# GateDriver.net
KiCad netlist of a schematic drawn in Altium Designer
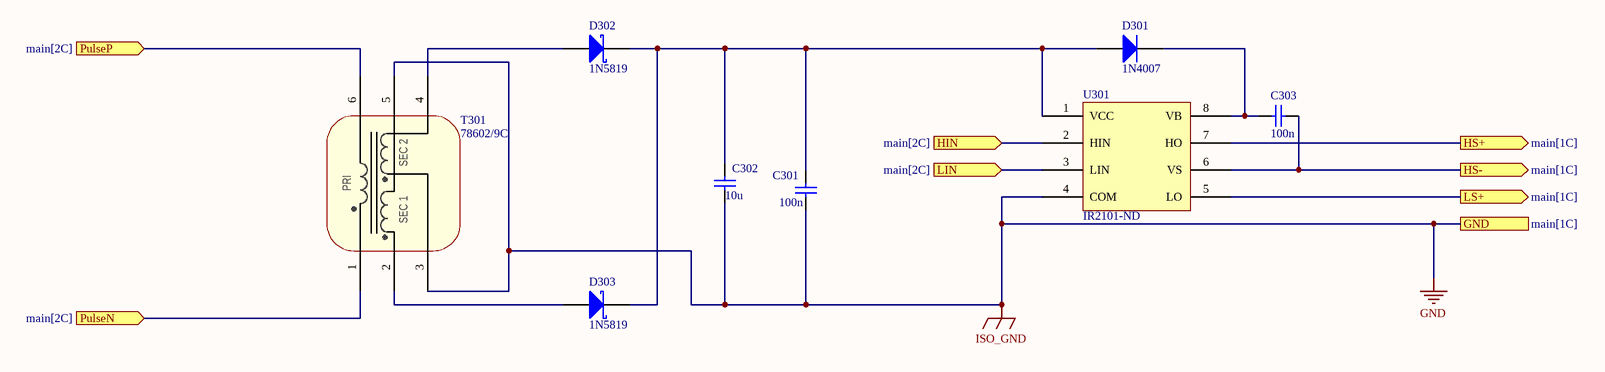
[diagram p0: GateDriver.SchDoc]

(export (version "E")
  (design (tool "Eeschema 10.0.6"))
  (components
    (comp (ref "C301")
      (value "100n")
      (footprint "CAP_1206")
      (description "Non Polarized Capacitor, SMD, 1206")
      (libsource (lib "Resistors and Capacitors") (part "CAPN 1206"))
    )
    (comp (ref "C302")
      (value "10u")
      (footprint "CAP_1206")
      (description "Non Polarized Capacitor, SMD, 1206")
      (libsource (lib "Resistors and Capacitors") (part "CAPN 1206"))
    )
    (comp (ref "C303")
      (value "100n")
      (footprint "RAD-0.2_AUT")
      (description "Non Polarized Capacitor, Multilayer Ceramic Dipped Radial, Pitch 200mil")
      (libsource (lib "Resistors and Capacitors") (part "CAPN RAD0.2"))
    )
    (comp (ref "D301")
      (value "1N4007")
      (footprint "DIODE0.4_AUT")
      (description "Diode, Standard, 1A, 1000v")
      (libsource (lib "Diodes") (part "1N4007"))
    )
    (comp (ref "D302")
      (value "1N5819")
      (footprint "DIODE0.4_AUT")
      (description "Schottky Diode, 1A,40v")
      (libsource (lib "Diodes") (part "1N5819"))
    )
    (comp (ref "D303")
      (value "1N5819")
      (footprint "DIODE0.4_AUT")
      (description "Schottky Diode, 1A,40v")
      (libsource (lib "Diodes") (part "1N5819"))
    )
    (comp (ref "T301")
      (value "78602/9C")
      (footprint "DIP6W_AUT")
      (description "Pulse transformer 1:1:1")
      (libsource (lib "Projects_2025") (part "78602/9C"))
    )
    (comp (ref "U301")
      (value "IR2101-ND")
      (footprint "DIP8-AUT")
      (description "Half-Bridge Gate Driver IC Non-Inverting 8-PDIP")
      (libsource (lib "Schematics") (part "IR2101-ND"))
    )
  )
  (nets
    (net (code "1") (name "/HIN") (class "Default")
      (node (ref "U301") (pin "2") (pinfunction "HIN_2") (pintype "passive"))
    )
    (net (code "2") (name "/HS+") (class "Default")
      (node (ref "U301") (pin "7") (pinfunction "HO_7") (pintype "passive"))
    )
    (net (code "3") (name "/HS-") (class "Default")
      (node (ref "C303") (pin "2") (pinfunction "2_2") (pintype "passive"))
      (node (ref "U301") (pin "6") (pinfunction "VS_6") (pintype "passive"))
    )
    (net (code "4") (name "/LIN") (class "Default")
      (node (ref "U301") (pin "3") (pinfunction "LIN_3") (pintype "passive"))
    )
    (net (code "5") (name "/LS+") (class "Default")
      (node (ref "U301") (pin "5") (pinfunction "LO_5") (pintype "passive"))
    )
    (net (code "6") (name "/PulseN") (class "Default")
      (node (ref "T301") (pin "1") (pinfunction "Pri_1_1") (pintype "power_in"))
    )
    (net (code "7") (name "/PulseP") (class "Default")
      (node (ref "T301") (pin "6") (pinfunction "Pri2_6") (pintype "power_in"))
    )
    (net (code "8") (name "GND") (class "Default")
      (node (ref "C301") (pin "1") (pinfunction "1_1") (pintype "passive"))
      (node (ref "C302") (pin "1") (pinfunction "1_1") (pintype "passive"))
      (node (ref "T301") (pin "3") (pinfunction "Sec1_2_3") (pintype "power_in"))
      (node (ref "T301") (pin "5") (pinfunction "Sec1_2_5") (pintype "power_in"))
      (node (ref "U301") (pin "4") (pinfunction "COM_4") (pintype "passive"))
    )
    (net (code "9") (name "Net-(T301-Sec1_1)") (class "Default")
      (node (ref "D303") (pin "A") (pinfunction "A_A") (pintype "passive"))
      (node (ref "T301") (pin "2") (pinfunction "Sec1_1_2") (pintype "power_in"))
    )
    (net (code "10") (name "Net-(T301-Sec2_2)") (class "Default")
      (node (ref "D302") (pin "A") (pinfunction "A_A") (pintype "passive"))
      (node (ref "T301") (pin "4") (pinfunction "Sec2_2_4") (pintype "power_in"))
    )
    (net (code "11") (name "Net-(U301-VB)") (class "Default")
      (node (ref "C303") (pin "1") (pinfunction "1_1") (pintype "passive"))
      (node (ref "D301") (pin "K") (pinfunction "K_K") (pintype "passive"))
      (node (ref "U301") (pin "8") (pinfunction "VB_8") (pintype "passive"))
    )
    (net (code "12") (name "Net-(U301-VCC)") (class "Default")
      (node (ref "C301") (pin "2") (pinfunction "2_2") (pintype "passive"))
      (node (ref "C302") (pin "2") (pinfunction "2_2") (pintype "passive"))
      (node (ref "D301") (pin "A") (pinfunction "A_A") (pintype "passive"))
      (node (ref "D302") (pin "K") (pinfunction "K_K") (pintype "passive"))
      (node (ref "D303") (pin "K") (pinfunction "K_K") (pintype "passive"))
      (node (ref "U301") (pin "1") (pinfunction "VCC_1") (pintype "passive"))
    )
  )
)
